# Datalogger.net
KiCad netlist of a schematic drawn in EAGLE
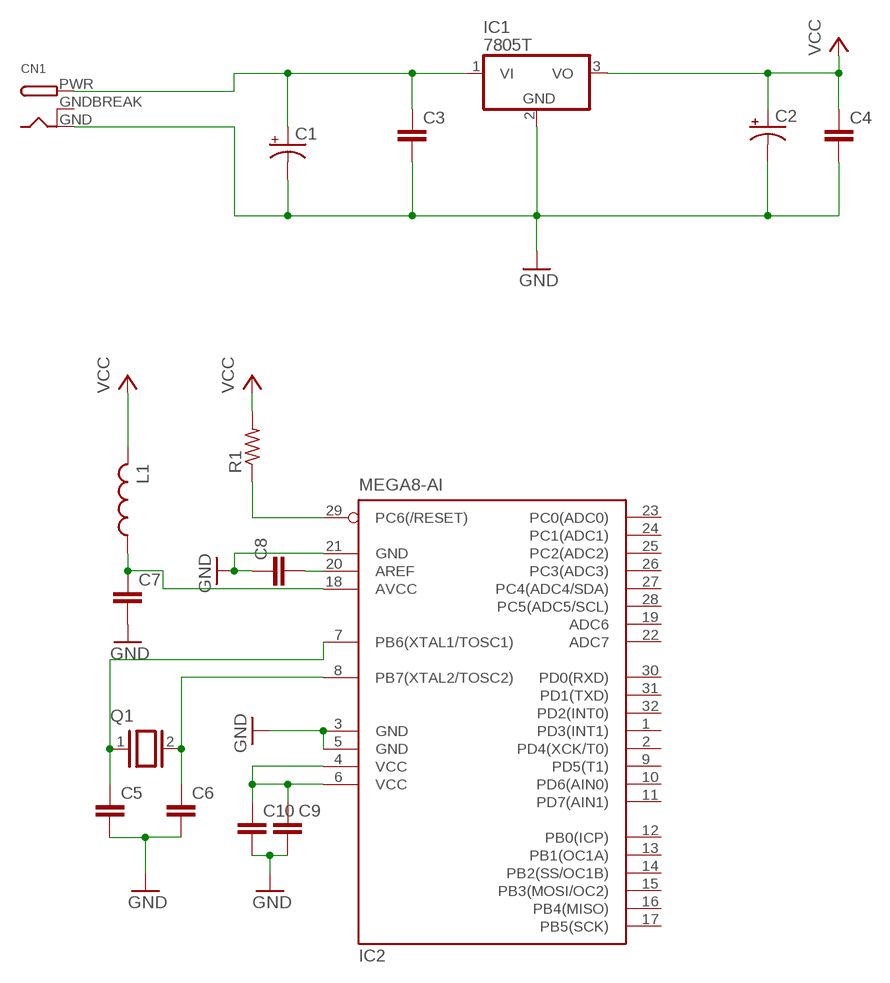
[diagram p0: schematic, sheet 1]

(export (version "E")
  (design (tool "Eeschema 10.0.6"))
  (components
    (comp (ref "C1")
      (value "CPOL-US140CLH-1010")
      (footprint "eagle-import:140CLH-1010")
      (libsource (lib "eagle-import") (part "CPOL-US140CLH-1010"))
    )
    (comp (ref "C2")
      (value "CPOL-US140CLH-1010")
      (footprint "eagle-import:140CLH-1010")
      (libsource (lib "eagle-import") (part "CPOL-US140CLH-1010"))
    )
    (comp (ref "C3")
      (value "C-EUC0603")
      (footprint "eagle-import:C0603")
      (libsource (lib "eagle-import") (part "C-EUC0603"))
    )
    (comp (ref "C4")
      (value "C-EUC0603")
      (footprint "eagle-import:C0603")
      (libsource (lib "eagle-import") (part "C-EUC0603"))
    )
    (comp (ref "C5")
      (value "C-EUC0603")
      (footprint "eagle-import:C0603")
      (libsource (lib "eagle-import") (part "C-EUC0603"))
    )
    (comp (ref "C6")
      (value "C-EUC0603")
      (footprint "eagle-import:C0603")
      (libsource (lib "eagle-import") (part "C-EUC0603"))
    )
    (comp (ref "C7")
      (value "C-EUC0603")
      (footprint "eagle-import:C0603")
      (libsource (lib "eagle-import") (part "C-EUC0603"))
    )
    (comp (ref "C8")
      (value "C-EUC0603")
      (footprint "eagle-import:C0603")
      (libsource (lib "eagle-import") (part "C-EUC0603"))
    )
    (comp (ref "C9")
      (value "C-EUC0603")
      (footprint "eagle-import:C0603")
      (libsource (lib "eagle-import") (part "C-EUC0603"))
    )
    (comp (ref "C10")
      (value "C-EUC0603")
      (footprint "eagle-import:C0603")
      (libsource (lib "eagle-import") (part "C-EUC0603"))
    )
    (comp (ref "CN1")
      (value "DCBARRELPTH")
      (footprint "eagle-import:DCJACK_2MM_PTH")
      (libsource (lib "eagle-import") (part "DCBARRELPTH"))
    )
    (comp (ref "IC1")
      (value "7805T")
      (footprint "eagle-import:TO220H")
      (libsource (lib "eagle-import") (part "78T05"))
    )
    (comp (ref "IC2")
      (value "MEGA8-AI")
      (footprint "eagle-import:TQFP32-08")
      (fields (field (name "MPN") "ATMEGA8-16AU"))
      (libsource (lib "eagle-import") (part "MEGA8-AI"))
    )
    (comp (ref "L1")
      (value "L-USL2012C")
      (footprint "eagle-import:L2012C")
      (libsource (lib "eagle-import") (part "L-USL2012C"))
    )
    (comp (ref "Q1")
      (value "XTAL/S")
      (footprint "eagle-import:QS")
      (libsource (lib "eagle-import") (part "XTAL/S"))
    )
    (comp (ref "R1")
      (value "R-US_R0603")
      (footprint "eagle-import:R0603")
      (libsource (lib "eagle-import") (part "R-US_R0603"))
    )
  )
  (nets
    (net (code "1") (name "/GNDBREAK") (class "Default")
      (node (ref "CN1") (pin "GNDBREAK") (pinfunction "GNDBREAK_GNDBREAK") (pintype "power_in"))
    )
    (net (code "2") (name "GND") (class "Default")
      (node (ref "C1") (pin "-") (pinfunction "-_-") (pintype "passive"))
      (node (ref "C10") (pin "2") (pinfunction "2_2") (pintype "passive"))
      (node (ref "C2") (pin "-") (pinfunction "-_-") (pintype "passive"))
      (node (ref "C3") (pin "2") (pinfunction "2_2") (pintype "passive"))
      (node (ref "C4") (pin "2") (pinfunction "2_2") (pintype "passive"))
      (node (ref "C5") (pin "2") (pinfunction "2_2") (pintype "passive"))
      (node (ref "C6") (pin "2") (pinfunction "2_2") (pintype "passive"))
      (node (ref "C7") (pin "2") (pinfunction "2_2") (pintype "passive"))
      (node (ref "C8") (pin "1") (pinfunction "1_1") (pintype "passive"))
      (node (ref "C9") (pin "2") (pinfunction "2_2") (pintype "passive"))
      (node (ref "CN1") (pin "GND") (pinfunction "GND_GND") (pintype "power_in"))
      (node (ref "IC1") (pin "2") (pinfunction "GND_2") (pintype "passive"))
      (node (ref "IC2") (pin "21") (pinfunction "GND_21") (pintype "power_in"))
      (node (ref "IC2") (pin "3") (pinfunction "GND_3") (pintype "power_in"))
      (node (ref "IC2") (pin "5") (pinfunction "GND_5") (pintype "power_in"))
    )
    (net (code "3") (name "Net-(C10-Pad1)") (class "Default")
      (node (ref "C10") (pin "1") (pinfunction "1_1") (pintype "passive"))
      (node (ref "C9") (pin "1") (pinfunction "1_1") (pintype "passive"))
      (node (ref "IC2") (pin "4") (pinfunction "VCC_4") (pintype "power_in"))
      (node (ref "IC2") (pin "6") (pinfunction "VCC_6") (pintype "power_in"))
    )
    (net (code "4") (name "Net-(IC1-VI)") (class "Default")
      (node (ref "C1") (pin "+") (pinfunction "+_+") (pintype "passive"))
      (node (ref "C3") (pin "1") (pinfunction "1_1") (pintype "passive"))
      (node (ref "CN1") (pin "PWR") (pinfunction "PWR_PWR") (pintype "power_in"))
      (node (ref "IC1") (pin "1") (pinfunction "VI_1") (pintype "input"))
    )
    (net (code "5") (name "Net-(IC2-AREF)") (class "Default")
      (node (ref "C8") (pin "2") (pinfunction "2_2") (pintype "passive"))
      (node (ref "IC2") (pin "20") (pinfunction "AREF_20") (pintype "passive"))
    )
    (net (code "6") (name "Net-(IC2-AVCC)") (class "Default")
      (node (ref "C7") (pin "1") (pinfunction "1_1") (pintype "passive"))
      (node (ref "IC2") (pin "18") (pinfunction "AVCC_18") (pintype "power_in"))
      (node (ref "L1") (pin "1") (pinfunction "1_1") (pintype "passive"))
    )
    (net (code "7") (name "Net-(IC2-PB6(XTAL1{slash}TOSC1))") (class "Default")
      (node (ref "C5") (pin "1") (pinfunction "1_1") (pintype "passive"))
      (node (ref "IC2") (pin "7") (pinfunction "PB6(XTAL1/TOSC1)_7") (pintype "bidirectional"))
      (node (ref "Q1") (pin "1") (pinfunction "1_1") (pintype "passive"))
    )
    (net (code "8") (name "Net-(IC2-PB7(XTAL2{slash}TOSC2))") (class "Default")
      (node (ref "C6") (pin "1") (pinfunction "1_1") (pintype "passive"))
      (node (ref "IC2") (pin "8") (pinfunction "PB7(XTAL2/TOSC2)_8") (pintype "bidirectional"))
      (node (ref "Q1") (pin "2") (pinfunction "2_2") (pintype "passive"))
    )
    (net (code "9") (name "Net-(IC2-PC6({slash}RESET))") (class "Default")
      (node (ref "IC2") (pin "29") (pinfunction "PC6(/RESET)_29") (pintype "bidirectional"))
      (node (ref "R1") (pin "1") (pinfunction "1_1") (pintype "passive"))
    )
    (net (code "10") (name "VCC") (class "Default")
      (node (ref "C2") (pin "+") (pinfunction "+_+") (pintype "passive"))
      (node (ref "C4") (pin "1") (pinfunction "1_1") (pintype "passive"))
      (node (ref "IC1") (pin "3") (pinfunction "VO_3") (pintype "passive"))
      (node (ref "L1") (pin "2") (pinfunction "2_2") (pintype "passive"))
      (node (ref "R1") (pin "2") (pinfunction "2_2") (pintype "passive"))
    )
    (net (code "11") (name "unconnected-(IC2-ADC6-Pad19)") (class "Default")
      (node (ref "IC2") (pin "19") (pinfunction "ADC6_19") (pintype "bidirectional"))
    )
    (net (code "12") (name "unconnected-(IC2-ADC7-Pad22)") (class "Default")
      (node (ref "IC2") (pin "22") (pinfunction "ADC7_22") (pintype "bidirectional"))
    )
    (net (code "13") (name "unconnected-(IC2-PB0(ICP)-Pad12)") (class "Default")
      (node (ref "IC2") (pin "12") (pinfunction "PB0(ICP)_12") (pintype "bidirectional"))
    )
    (net (code "14") (name "unconnected-(IC2-PB1(OC1A)-Pad13)") (class "Default")
      (node (ref "IC2") (pin "13") (pinfunction "PB1(OC1A)_13") (pintype "bidirectional"))
    )
    (net (code "15") (name "unconnected-(IC2-PB2(SS{slash}OC1B)-Pad14)") (class "Default")
      (node (ref "IC2") (pin "14") (pinfunction "PB2(SS/OC1B)_14") (pintype "bidirectional"))
    )
    (net (code "16") (name "unconnected-(IC2-PB3(MOSI{slash}OC2)-Pad15)") (class "Default")
      (node (ref "IC2") (pin "15") (pinfunction "PB3(MOSI/OC2)_15") (pintype "bidirectional"))
    )
    (net (code "17") (name "unconnected-(IC2-PB4(MISO)-Pad16)") (class "Default")
      (node (ref "IC2") (pin "16") (pinfunction "PB4(MISO)_16") (pintype "bidirectional"))
    )
    (net (code "18") (name "unconnected-(IC2-PB5(SCK)-Pad17)") (class "Default")
      (node (ref "IC2") (pin "17") (pinfunction "PB5(SCK)_17") (pintype "bidirectional"))
    )
    (net (code "19") (name "unconnected-(IC2-PC0(ADC0)-Pad23)") (class "Default")
      (node (ref "IC2") (pin "23") (pinfunction "PC0(ADC0)_23") (pintype "bidirectional"))
    )
    (net (code "20") (name "unconnected-(IC2-PC1(ADC1)-Pad24)") (class "Default")
      (node (ref "IC2") (pin "24") (pinfunction "PC1(ADC1)_24") (pintype "bidirectional"))
    )
    (net (code "21") (name "unconnected-(IC2-PC2(ADC2)-Pad25)") (class "Default")
      (node (ref "IC2") (pin "25") (pinfunction "PC2(ADC2)_25") (pintype "bidirectional"))
    )
    (net (code "22") (name "unconnected-(IC2-PC3(ADC3)-Pad26)") (class "Default")
      (node (ref "IC2") (pin "26") (pinfunction "PC3(ADC3)_26") (pintype "bidirectional"))
    )
    (net (code "23") (name "unconnected-(IC2-PC4(ADC4{slash}SDA)-Pad27)") (class "Default")
      (node (ref "IC2") (pin "27") (pinfunction "PC4(ADC4/SDA)_27") (pintype "bidirectional"))
    )
    (net (code "24") (name "unconnected-(IC2-PC5(ADC5{slash}SCL)-Pad28)") (class "Default")
      (node (ref "IC2") (pin "28") (pinfunction "PC5(ADC5/SCL)_28") (pintype "bidirectional"))
    )
    (net (code "25") (name "unconnected-(IC2-PD0(RXD)-Pad30)") (class "Default")
      (node (ref "IC2") (pin "30") (pinfunction "PD0(RXD)_30") (pintype "bidirectional"))
    )
    (net (code "26") (name "unconnected-(IC2-PD1(TXD)-Pad31)") (class "Default")
      (node (ref "IC2") (pin "31") (pinfunction "PD1(TXD)_31") (pintype "bidirectional"))
    )
    (net (code "27") (name "unconnected-(IC2-PD2(INT0)-Pad32)") (class "Default")
      (node (ref "IC2") (pin "32") (pinfunction "PD2(INT0)_32") (pintype "bidirectional"))
    )
    (net (code "28") (name "unconnected-(IC2-PD3(INT1)-Pad1)") (class "Default")
      (node (ref "IC2") (pin "1") (pinfunction "PD3(INT1)_1") (pintype "bidirectional"))
    )
    (net (code "29") (name "unconnected-(IC2-PD4(XCK{slash}T0)-Pad2)") (class "Default")
      (node (ref "IC2") (pin "2") (pinfunction "PD4(XCK/T0)_2") (pintype "bidirectional"))
    )
    (net (code "30") (name "unconnected-(IC2-PD5(T1)-Pad9)") (class "Default")
      (node (ref "IC2") (pin "9") (pinfunction "PD5(T1)_9") (pintype "bidirectional"))
    )
    (net (code "31") (name "unconnected-(IC2-PD6(AIN0)-Pad10)") (class "Default")
      (node (ref "IC2") (pin "10") (pinfunction "PD6(AIN0)_10") (pintype "bidirectional"))
    )
    (net (code "32") (name "unconnected-(IC2-PD7(AIN1)-Pad11)") (class "Default")
      (node (ref "IC2") (pin "11") (pinfunction "PD7(AIN1)_11") (pintype "bidirectional"))
    )
  )
)
